# 555-timer-CD4017BE.net
KiCad netlist of a schematic drawn in EasyEDA Pro
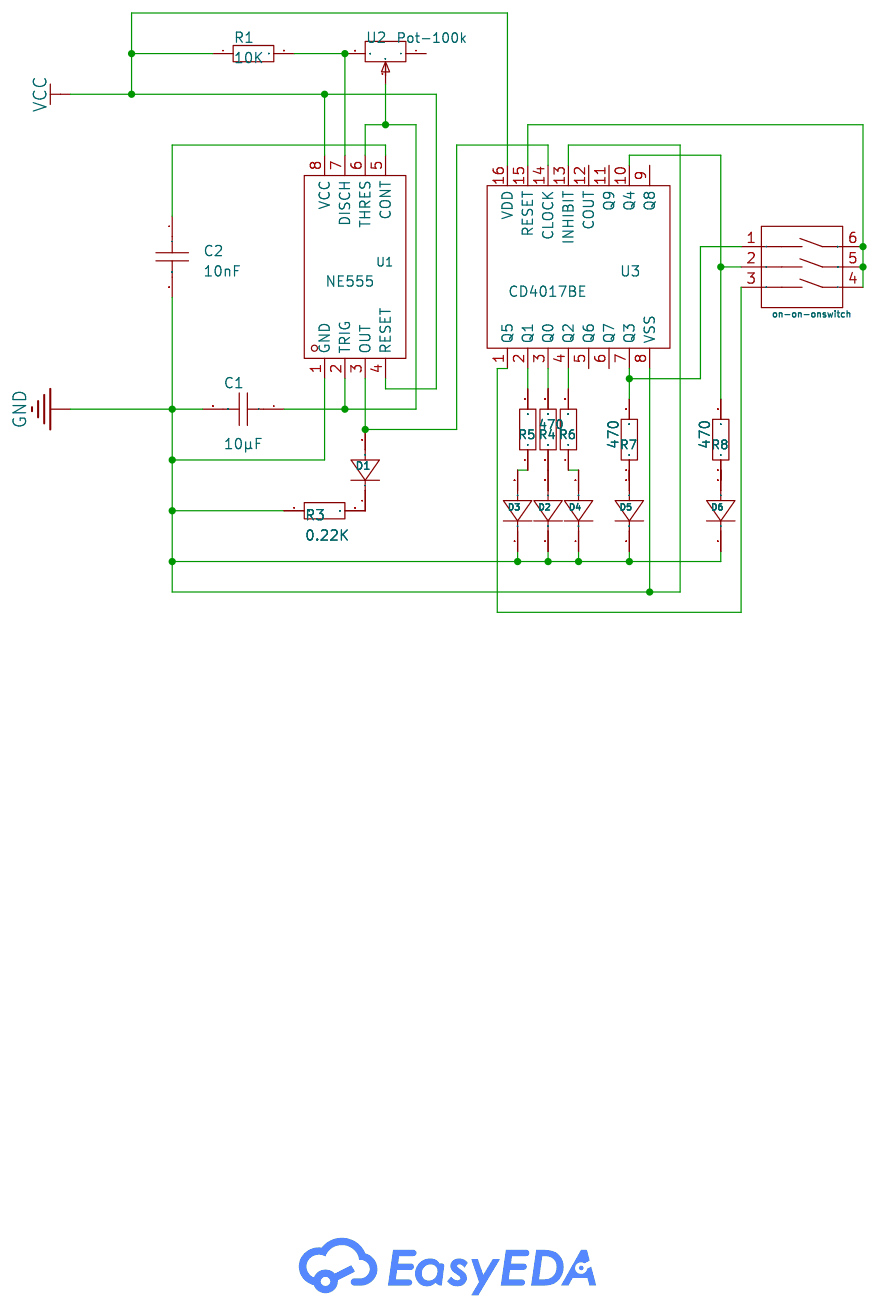
[diagram p0: schematic sheet]

(export (version "E")
  (design (tool "Eeschema 10.0.6"))
  (components
    (comp (ref "C1")
      (value "10µF")
      (footprint "easyedapro:C0603")
      (libsource (lib "easyedapro") (part "CAP"))
    )
    (comp (ref "C2")
      (value "10nF")
      (footprint "easyedapro:C0603")
      (libsource (lib "easyedapro") (part "CAP"))
    )
    (comp (ref "D1")
      (value "~")
      (footprint "easyedapro:SMA_L4.4-W2.8-LS5.4-RD")
      (libsource (lib "easyedapro") (part "D_1N4007"))
    )
    (comp (ref "D2")
      (value "~")
      (footprint "easyedapro:SMA_L4.4-W2.8-LS5.4-RD")
      (libsource (lib "easyedapro") (part "D_1N4007"))
    )
    (comp (ref "D3")
      (value "~")
      (footprint "easyedapro:SMA_L4.4-W2.8-LS5.4-RD")
      (libsource (lib "easyedapro") (part "D_1N4007"))
    )
    (comp (ref "D4")
      (value "~")
      (footprint "easyedapro:SMA_L4.4-W2.8-LS5.4-RD")
      (libsource (lib "easyedapro") (part "D_1N4007"))
    )
    (comp (ref "D5")
      (value "~")
      (footprint "easyedapro:SMA_L4.4-W2.8-LS5.4-RD")
      (libsource (lib "easyedapro") (part "D_1N4007"))
    )
    (comp (ref "D6")
      (value "~")
      (footprint "easyedapro:SMA_L4.4-W2.8-LS5.4-RD")
      (libsource (lib "easyedapro") (part "D_1N4007"))
    )
    (comp (ref "on-on-onswitch")
      (value "ATE2D-2M3-10-Z")
      (footprint "easyedapro:SW-TH_ATE2D-2M3-10-Z")
      (fields (field (name "Manufacturer") "NIDEC(尼得科)"))
      (libsource (lib "easyedapro") (part "ATE2D-2M3-10-Z"))
    )
    (comp (ref "R1") (value "10K") (footprint "easyedapro:R0603") (libsource (lib "easyedapro") (part "Res")))
    (comp (ref "R3")
      (value "0.22K")
      (footprint "easyedapro:R0603")
      (libsource (lib "easyedapro") (part "Res"))
    )
    (comp (ref "R4") (value "470") (footprint "easyedapro:R0603") (libsource (lib "easyedapro") (part "Res")))
    (comp (ref "R5") (value "470") (footprint "easyedapro:R0603") (libsource (lib "easyedapro") (part "Res")))
    (comp (ref "R6") (value "470") (footprint "easyedapro:R0603") (libsource (lib "easyedapro") (part "Res")))
    (comp (ref "R7") (value "470") (footprint "easyedapro:R0603") (libsource (lib "easyedapro") (part "Res")))
    (comp (ref "R8") (value "470") (footprint "easyedapro:R0603") (libsource (lib "easyedapro") (part "Res")))
    (comp (ref "U1")
      (value "NE555")
      (footprint "easyedapro:SOIC-8_L4.9-W3.9-P1.27-LS6.0-BL")
      (fields (field (name "Manufacturer") "IDCHIP(英锐芯)"))
      (libsource (lib "easyedapro") (part "NE555_C5125085"))
    )
    (comp (ref "U2")
      (value "Pot-100k")
      (footprint "easyedapro:RES-ADJ-SMD_VG039NCH")
      (libsource (lib "easyedapro") (part "3*3POTENTIOMETER-10KΩ20%"))
    )
    (comp (ref "U3")
      (value "CD4017BE")
      (footprint "easyedapro:DIP-16_L19.2-W6.6-P2.54-LS7.6-BL")
      (fields (field (name "Manufacturer") "HGSEMI(华冠)"))
      (libsource (lib "easyedapro") (part "CD4017BE_C507168"))
    )
  )
  (nets
    (net (code "1") (name "GND") (class "Default")
      (node (ref "C1") (pin "2") (pinfunction "2_2") (pintype "input"))
      (node (ref "C2") (pin "2") (pinfunction "2_2") (pintype "input"))
      (node (ref "D2") (pin "1") (pinfunction "K_1") (pintype "input"))
      (node (ref "D3") (pin "1") (pinfunction "K_1") (pintype "input"))
      (node (ref "D4") (pin "1") (pinfunction "K_1") (pintype "input"))
      (node (ref "D5") (pin "1") (pinfunction "K_1") (pintype "input"))
      (node (ref "D6") (pin "1") (pinfunction "K_1") (pintype "input"))
      (node (ref "R3") (pin "1") (pinfunction "1_1") (pintype "input"))
      (node (ref "U1") (pin "1") (pinfunction "GND_1") (pintype "input"))
      (node (ref "U3") (pin "13") (pinfunction "INHIBIT_13") (pintype "unspecified"))
      (node (ref "U3") (pin "8") (pinfunction "VSS_8") (pintype "unspecified"))
    )
    (net (code "2") (name "Net-(D1-A)") (class "Default")
      (node (ref "D1") (pin "2") (pinfunction "A_2") (pintype "input"))
      (node (ref "U1") (pin "3") (pinfunction "OUT_3") (pintype "input"))
      (node (ref "U3") (pin "14") (pinfunction "CLOCK_14") (pintype "unspecified"))
    )
    (net (code "3") (name "Net-(D1-K)") (class "Default")
      (node (ref "D1") (pin "1") (pinfunction "K_1") (pintype "input"))
      (node (ref "R3") (pin "2") (pinfunction "2_2") (pintype "input"))
    )
    (net (code "4") (name "Net-(D2-A)") (class "Default")
      (node (ref "D2") (pin "2") (pinfunction "A_2") (pintype "input"))
      (node (ref "R4") (pin "1") (pinfunction "1_1") (pintype "input"))
    )
    (net (code "5") (name "Net-(D3-A)") (class "Default")
      (node (ref "D3") (pin "2") (pinfunction "A_2") (pintype "input"))
      (node (ref "R5") (pin "1") (pinfunction "1_1") (pintype "input"))
    )
    (net (code "6") (name "Net-(D4-A)") (class "Default")
      (node (ref "D4") (pin "2") (pinfunction "A_2") (pintype "input"))
      (node (ref "R6") (pin "1") (pinfunction "1_1") (pintype "input"))
    )
    (net (code "7") (name "Net-(D5-A)") (class "Default")
      (node (ref "D5") (pin "2") (pinfunction "A_2") (pintype "input"))
      (node (ref "R7") (pin "1") (pinfunction "1_1") (pintype "input"))
    )
    (net (code "8") (name "Net-(D6-A)") (class "Default")
      (node (ref "D6") (pin "2") (pinfunction "A_2") (pintype "input"))
      (node (ref "R8") (pin "1") (pinfunction "1_1") (pintype "input"))
    )
    (net (code "9") (name "Net-(U1-CONT)") (class "Default")
      (node (ref "C2") (pin "1") (pinfunction "1_1") (pintype "input"))
      (node (ref "U1") (pin "5") (pinfunction "CONT_5") (pintype "input"))
    )
    (net (code "10") (name "Net-(U1-DISCH)") (class "Default")
      (node (ref "R1") (pin "2") (pinfunction "2_2") (pintype "input"))
      (node (ref "U1") (pin "7") (pinfunction "DISCH_7") (pintype "input"))
      (node (ref "U2") (pin "3") (pinfunction "3_3") (pintype "input"))
    )
    (net (code "11") (name "Net-(U1-THRES)") (class "Default")
      (node (ref "C1") (pin "1") (pinfunction "1_1") (pintype "input"))
      (node (ref "U1") (pin "2") (pinfunction "TRIG_2") (pintype "input"))
      (node (ref "U1") (pin "6") (pinfunction "THRES_6") (pintype "input"))
      (node (ref "U2") (pin "2") (pinfunction "2_2") (pintype "input"))
    )
    (net (code "12") (name "Net-(U3-Q0)") (class "Default")
      (node (ref "R4") (pin "2") (pinfunction "2_2") (pintype "input"))
      (node (ref "U3") (pin "3") (pinfunction "Q0_3") (pintype "unspecified"))
    )
    (net (code "13") (name "Net-(U3-Q1)") (class "Default")
      (node (ref "R5") (pin "2") (pinfunction "2_2") (pintype "input"))
      (node (ref "U3") (pin "2") (pinfunction "Q1_2") (pintype "unspecified"))
    )
    (net (code "14") (name "Net-(U3-Q2)") (class "Default")
      (node (ref "R6") (pin "2") (pinfunction "2_2") (pintype "input"))
      (node (ref "U3") (pin "4") (pinfunction "Q2_4") (pintype "unspecified"))
    )
    (net (code "15") (name "Net-(U3-Q3)") (class "Default")
      (node (ref "R7") (pin "2") (pinfunction "2_2") (pintype "input"))
      (node (ref "U3") (pin "7") (pinfunction "Q3_7") (pintype "unspecified"))
      (node (ref "on-on-onswitch") (pin "1") (pinfunction "1_1") (pintype "unspecified"))
    )
    (net (code "16") (name "Net-(U3-Q4)") (class "Default")
      (node (ref "R8") (pin "2") (pinfunction "2_2") (pintype "input"))
      (node (ref "U3") (pin "10") (pinfunction "Q4_10") (pintype "unspecified"))
      (node (ref "on-on-onswitch") (pin "2") (pinfunction "2_2") (pintype "unspecified"))
    )
    (net (code "17") (name "Net-(U3-Q5)") (class "Default")
      (node (ref "U3") (pin "1") (pinfunction "Q5_1") (pintype "unspecified"))
      (node (ref "on-on-onswitch") (pin "3") (pinfunction "3_3") (pintype "unspecified"))
    )
    (net (code "18") (name "Net-(U3-RESET)") (class "Default")
      (node (ref "U3") (pin "15") (pinfunction "RESET_15") (pintype "unspecified"))
      (node (ref "on-on-onswitch") (pin "4") (pinfunction "4_4") (pintype "unspecified"))
      (node (ref "on-on-onswitch") (pin "5") (pinfunction "5_5") (pintype "unspecified"))
      (node (ref "on-on-onswitch") (pin "6") (pinfunction "6_6") (pintype "unspecified"))
    )
    (net (code "19") (name "VCC") (class "Default")
      (node (ref "R1") (pin "1") (pinfunction "1_1") (pintype "input"))
      (node (ref "U1") (pin "4") (pinfunction "RESET_4") (pintype "input"))
      (node (ref "U1") (pin "8") (pinfunction "VCC_8") (pintype "input"))
      (node (ref "U3") (pin "16") (pinfunction "VDD_16") (pintype "unspecified"))
    )
    (net (code "20") (name "unconnected-(U2-Pad1)") (class "Default")
      (node (ref "U2") (pin "1") (pinfunction "1_1") (pintype "input"))
    )
    (net (code "21") (name "unconnected-(U3-COUT-Pad12)") (class "Default")
      (node (ref "U3") (pin "12") (pinfunction "COUT_12") (pintype "unspecified"))
    )
    (net (code "22") (name "unconnected-(U3-Q6-Pad5)") (class "Default")
      (node (ref "U3") (pin "5") (pinfunction "Q6_5") (pintype "unspecified"))
    )
    (net (code "23") (name "unconnected-(U3-Q7-Pad6)") (class "Default")
      (node (ref "U3") (pin "6") (pinfunction "Q7_6") (pintype "unspecified"))
    )
    (net (code "24") (name "unconnected-(U3-Q8-Pad9)") (class "Default")
      (node (ref "U3") (pin "9") (pinfunction "Q8_9") (pintype "unspecified"))
    )
    (net (code "25") (name "unconnected-(U3-Q9-Pad11)") (class "Default")
      (node (ref "U3") (pin "11") (pinfunction "Q9_11") (pintype "unspecified"))
    )
  )
)
